# SRAM1.net
KiCad netlist of a schematic drawn in Altium Designer
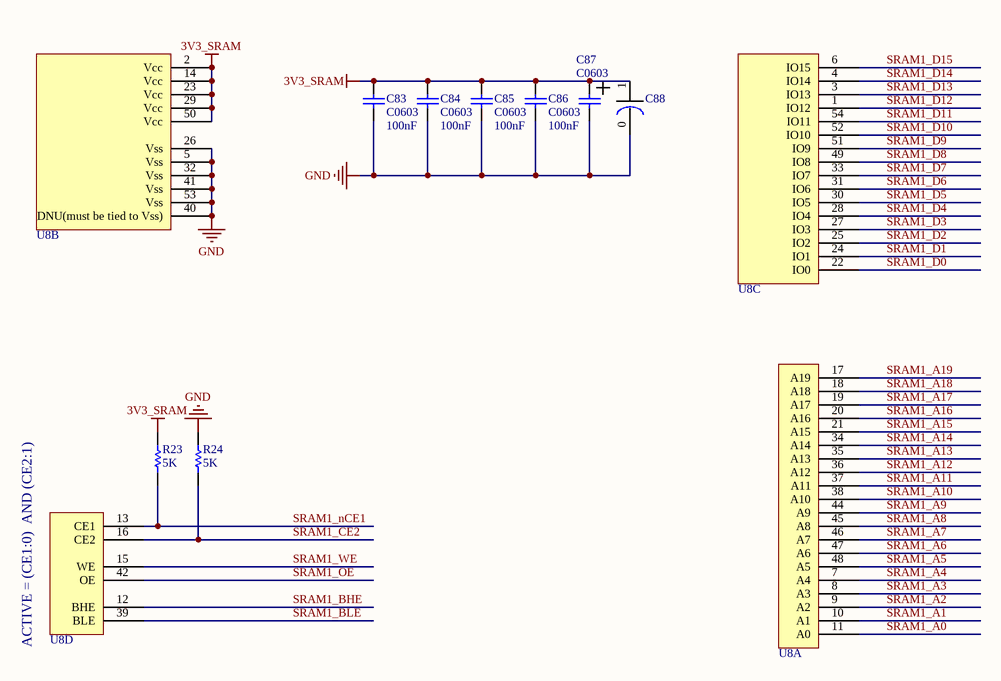
[diagram p0: SRAM1.SchDoc]

(export (version "E")
  (design (tool "Eeschema 10.0.6"))
  (components
    (comp (ref "C83")
      (value "C0603")
      (footprint "0603")
      (description "Ceramic Chip Capacitor - Standard")
      (fields (field (name "ALTIUM_VALUE") "100nF") (field (name "PUBLISHER") "Altium Limited"))
      (libsource (lib "KEMET Chip Capacitor") (part "C0603"))
    )
    (comp (ref "C84")
      (value "C0603")
      (footprint "0603")
      (description "Ceramic Chip Capacitor - Standard")
      (fields (field (name "ALTIUM_VALUE") "100nF") (field (name "PUBLISHER") "Altium Limited"))
      (libsource (lib "KEMET Chip Capacitor") (part "C0603"))
    )
    (comp (ref "C85")
      (value "C0603")
      (footprint "0603")
      (description "Ceramic Chip Capacitor - Standard")
      (fields (field (name "ALTIUM_VALUE") "100nF") (field (name "PUBLISHER") "Altium Limited"))
      (libsource (lib "KEMET Chip Capacitor") (part "C0603"))
    )
    (comp (ref "C86")
      (value "C0603")
      (footprint "0603")
      (description "Ceramic Chip Capacitor - Standard")
      (fields (field (name "ALTIUM_VALUE") "100nF") (field (name "PUBLISHER") "Altium Limited"))
      (libsource (lib "KEMET Chip Capacitor") (part "C0603"))
    )
    (comp (ref "C87")
      (value "C0603")
      (footprint "0603")
      (description "Ceramic Chip Capacitor - Standard")
      (fields (field (name "PUBLISHER") "Altium Limited"))
      (libsource (lib "KEMET Chip Capacitor") (part "C0603"))
    )
    (comp (ref "C88")
      (value "Electrolytic SMD Cap")
      (footprint "22_47u_10A")
      (libsource (lib "SMD_ELECTRLT_CAP") (part "Electrolytic SMD Cap"))
    )
    (comp (ref "R23")
      (value "5K")
      (footprint "ERA-0805")
      (fields (field (name "PUBLISHER") "Altium Limited"))
      (libsource (lib "Panasonic Resistor") (part "ERA6Y"))
    )
    (comp (ref "R24")
      (value "5K")
      (footprint "ERA-0805")
      (fields (field (name "PUBLISHER") "Altium Limited"))
      (libsource (lib "Panasonic Resistor") (part "ERA6Y"))
    )
    (comp (ref "U8")
      (value "SRAM")
      (footprint "PCBComponent_1")
      (description "Static RAM")
      (libsource (lib "cy7c1061av33") (part "CY7C1061AV33"))
    )
  )
  (nets
    (net (code "1") (name "/SRAM1_A0") (class "Default")
      (node (ref "U8") (pin "11") (pinfunction "A0_11") (pintype "passive"))
    )
    (net (code "2") (name "/SRAM1_A1") (class "Default")
      (node (ref "U8") (pin "10") (pinfunction "A1_10") (pintype "passive"))
    )
    (net (code "3") (name "/SRAM1_A2") (class "Default")
      (node (ref "U8") (pin "9") (pinfunction "A2_9") (pintype "passive"))
    )
    (net (code "4") (name "/SRAM1_A3") (class "Default")
      (node (ref "U8") (pin "8") (pinfunction "A3_8") (pintype "passive"))
    )
    (net (code "5") (name "/SRAM1_A4") (class "Default")
      (node (ref "U8") (pin "7") (pinfunction "A4_7") (pintype "passive"))
    )
    (net (code "6") (name "/SRAM1_A5") (class "Default")
      (node (ref "U8") (pin "48") (pinfunction "A5_48") (pintype "passive"))
    )
    (net (code "7") (name "/SRAM1_A6") (class "Default")
      (node (ref "U8") (pin "47") (pinfunction "A6_47") (pintype "passive"))
    )
    (net (code "8") (name "/SRAM1_A7") (class "Default")
      (node (ref "U8") (pin "46") (pinfunction "A7_46") (pintype "passive"))
    )
    (net (code "9") (name "/SRAM1_A8") (class "Default")
      (node (ref "U8") (pin "45") (pinfunction "A8_45") (pintype "passive"))
    )
    (net (code "10") (name "/SRAM1_A9") (class "Default")
      (node (ref "U8") (pin "44") (pinfunction "A9_44") (pintype "passive"))
    )
    (net (code "11") (name "/SRAM1_A10") (class "Default")
      (node (ref "U8") (pin "38") (pinfunction "A10_38") (pintype "passive"))
    )
    (net (code "12") (name "/SRAM1_A11") (class "Default")
      (node (ref "U8") (pin "37") (pinfunction "A11_37") (pintype "passive"))
    )
    (net (code "13") (name "/SRAM1_A12") (class "Default")
      (node (ref "U8") (pin "36") (pinfunction "A12_36") (pintype "passive"))
    )
    (net (code "14") (name "/SRAM1_A13") (class "Default")
      (node (ref "U8") (pin "35") (pinfunction "A13_35") (pintype "passive"))
    )
    (net (code "15") (name "/SRAM1_A14") (class "Default")
      (node (ref "U8") (pin "34") (pinfunction "A14_34") (pintype "passive"))
    )
    (net (code "16") (name "/SRAM1_A15") (class "Default")
      (node (ref "U8") (pin "21") (pinfunction "A15_21") (pintype "passive"))
    )
    (net (code "17") (name "/SRAM1_A16") (class "Default")
      (node (ref "U8") (pin "20") (pinfunction "A16_20") (pintype "passive"))
    )
    (net (code "18") (name "/SRAM1_A17") (class "Default")
      (node (ref "U8") (pin "19") (pinfunction "A17_19") (pintype "passive"))
    )
    (net (code "19") (name "/SRAM1_A18") (class "Default")
      (node (ref "U8") (pin "18") (pinfunction "A18_18") (pintype "passive"))
    )
    (net (code "20") (name "/SRAM1_A19") (class "Default")
      (node (ref "U8") (pin "17") (pinfunction "A19_17") (pintype "passive"))
    )
    (net (code "21") (name "/SRAM1_BHE") (class "Default")
      (node (ref "U8") (pin "12") (pinfunction "BHE_12") (pintype "passive"))
    )
    (net (code "22") (name "/SRAM1_BLE") (class "Default")
      (node (ref "U8") (pin "39") (pinfunction "BLE_39") (pintype "passive"))
    )
    (net (code "23") (name "/SRAM1_CE2") (class "Default")
      (node (ref "R24") (pin "1") (pinfunction "1_1") (pintype "passive"))
      (node (ref "U8") (pin "16") (pinfunction "CE2_16") (pintype "passive"))
    )
    (net (code "24") (name "/SRAM1_D0") (class "Default")
      (node (ref "U8") (pin "22") (pinfunction "IO0_22") (pintype "passive"))
    )
    (net (code "25") (name "/SRAM1_D1") (class "Default")
      (node (ref "U8") (pin "24") (pinfunction "IO1_24") (pintype "passive"))
    )
    (net (code "26") (name "/SRAM1_D2") (class "Default")
      (node (ref "U8") (pin "25") (pinfunction "IO2_25") (pintype "passive"))
    )
    (net (code "27") (name "/SRAM1_D3") (class "Default")
      (node (ref "U8") (pin "27") (pinfunction "IO3_27") (pintype "passive"))
    )
    (net (code "28") (name "/SRAM1_D4") (class "Default")
      (node (ref "U8") (pin "28") (pinfunction "IO4_28") (pintype "passive"))
    )
    (net (code "29") (name "/SRAM1_D5") (class "Default")
      (node (ref "U8") (pin "30") (pinfunction "IO5_30") (pintype "passive"))
    )
    (net (code "30") (name "/SRAM1_D6") (class "Default")
      (node (ref "U8") (pin "31") (pinfunction "IO6_31") (pintype "passive"))
    )
    (net (code "31") (name "/SRAM1_D7") (class "Default")
      (node (ref "U8") (pin "33") (pinfunction "IO7_33") (pintype "passive"))
    )
    (net (code "32") (name "/SRAM1_D8") (class "Default")
      (node (ref "U8") (pin "49") (pinfunction "IO8_49") (pintype "passive"))
    )
    (net (code "33") (name "/SRAM1_D9") (class "Default")
      (node (ref "U8") (pin "51") (pinfunction "IO9_51") (pintype "passive"))
    )
    (net (code "34") (name "/SRAM1_D10") (class "Default")
      (node (ref "U8") (pin "52") (pinfunction "IO10_52") (pintype "passive"))
    )
    (net (code "35") (name "/SRAM1_D11") (class "Default")
      (node (ref "U8") (pin "54") (pinfunction "IO11_54") (pintype "passive"))
    )
    (net (code "36") (name "/SRAM1_D12") (class "Default")
      (node (ref "U8") (pin "1") (pinfunction "IO12_1") (pintype "passive"))
    )
    (net (code "37") (name "/SRAM1_D13") (class "Default")
      (node (ref "U8") (pin "3") (pinfunction "IO13_3") (pintype "passive"))
    )
    (net (code "38") (name "/SRAM1_D14") (class "Default")
      (node (ref "U8") (pin "4") (pinfunction "IO14_4") (pintype "passive"))
    )
    (net (code "39") (name "/SRAM1_D15") (class "Default")
      (node (ref "U8") (pin "6") (pinfunction "IO15_6") (pintype "passive"))
    )
    (net (code "40") (name "/SRAM1_OE") (class "Default")
      (node (ref "U8") (pin "42") (pinfunction "OE_42") (pintype "passive"))
    )
    (net (code "41") (name "/SRAM1_WE") (class "Default")
      (node (ref "U8") (pin "15") (pinfunction "WE_15") (pintype "passive"))
    )
    (net (code "42") (name "/SRAM1_nCE1") (class "Default")
      (node (ref "R23") (pin "1") (pinfunction "1_1") (pintype "passive"))
      (node (ref "U8") (pin "13") (pinfunction "CE1_13") (pintype "passive"))
    )
    (net (code "43") (name "3V3_SRAM") (class "Default")
      (node (ref "C83") (pin "2") (pinfunction "2_2") (pintype "passive"))
      (node (ref "C84") (pin "2") (pinfunction "2_2") (pintype "passive"))
      (node (ref "C85") (pin "2") (pinfunction "2_2") (pintype "passive"))
      (node (ref "C86") (pin "2") (pinfunction "2_2") (pintype "passive"))
      (node (ref "C87") (pin "2") (pinfunction "2_2") (pintype "passive"))
      (node (ref "C88") (pin "1") (pinfunction "1_1") (pintype "passive"))
      (node (ref "R23") (pin "2") (pinfunction "2_2") (pintype "passive"))
      (node (ref "U8") (pin "14") (pinfunction "Vcc_14") (pintype "power_in"))
      (node (ref "U8") (pin "2") (pinfunction "Vcc_2") (pintype "power_in"))
      (node (ref "U8") (pin "23") (pinfunction "Vcc_23") (pintype "power_in"))
      (node (ref "U8") (pin "29") (pinfunction "Vcc_29") (pintype "power_in"))
      (node (ref "U8") (pin "50") (pinfunction "Vcc_50") (pintype "power_in"))
    )
    (net (code "44") (name "GND") (class "Default")
      (node (ref "C83") (pin "1") (pinfunction "1_1") (pintype "passive"))
      (node (ref "C84") (pin "1") (pinfunction "1_1") (pintype "passive"))
      (node (ref "C85") (pin "1") (pinfunction "1_1") (pintype "passive"))
      (node (ref "C86") (pin "1") (pinfunction "1_1") (pintype "passive"))
      (node (ref "C87") (pin "1") (pinfunction "1_1") (pintype "passive"))
      (node (ref "C88") (pin "0") (pinfunction "0_0") (pintype "passive"))
      (node (ref "R24") (pin "2") (pinfunction "2_2") (pintype "passive"))
      (node (ref "U8") (pin "26") (pinfunction "Vss_26") (pintype "power_in"))
      (node (ref "U8") (pin "32") (pinfunction "Vss_32") (pintype "power_in"))
      (node (ref "U8") (pin "40") (pinfunction "DNU(must_be_tied_to_Vss)_40") (pintype "passive"))
      (node (ref "U8") (pin "41") (pinfunction "Vss_41") (pintype "passive"))
      (node (ref "U8") (pin "5") (pinfunction "Vss_5") (pintype "power_in"))
      (node (ref "U8") (pin "53") (pinfunction "Vss_53") (pintype "power_in"))
    )
  )
)
